# Adafruit_NeoPixel_FeatherWing.net
KiCad netlist of a schematic drawn in EAGLE
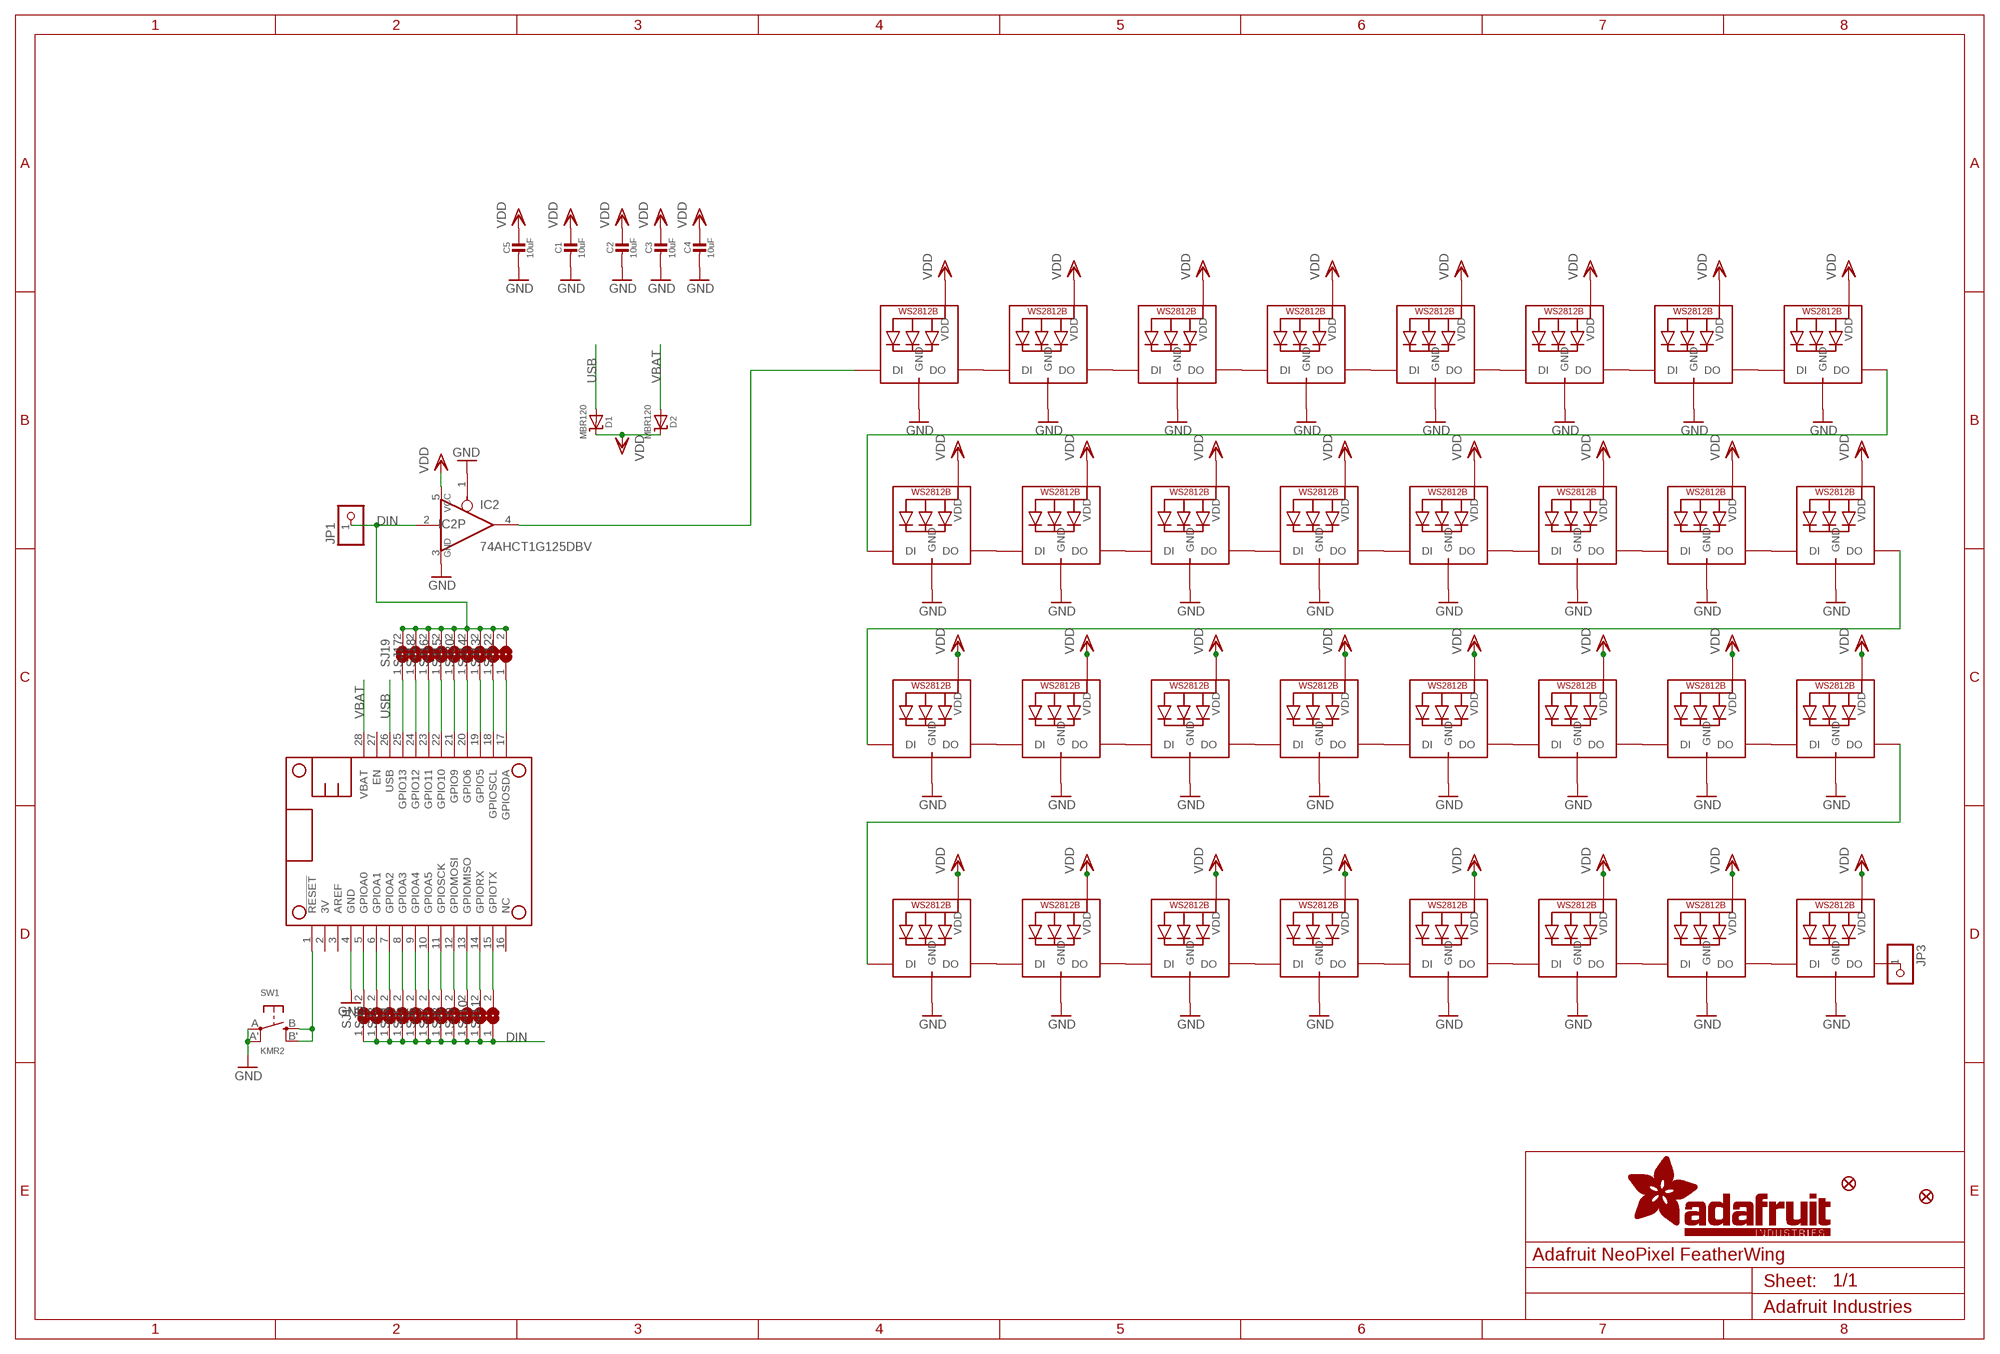
[diagram p0: schematic, sheet 1]

(export (version "E")
  (design (tool "Eeschema 10.0.6"))
  (components
    (comp (ref "C1")
      (value "10uF")
      (footprint "eagle-import:0805-NO")
      (libsource (lib "eagle-import") (part "CAP_CERAMIC0805-NOOUTLINE"))
    )
    (comp (ref "C2")
      (value "10uF")
      (footprint "eagle-import:0805-NO")
      (libsource (lib "eagle-import") (part "CAP_CERAMIC0805-NOOUTLINE"))
    )
    (comp (ref "C3")
      (value "10uF")
      (footprint "eagle-import:0805-NO")
      (libsource (lib "eagle-import") (part "CAP_CERAMIC0805-NOOUTLINE"))
    )
    (comp (ref "C4")
      (value "10uF")
      (footprint "eagle-import:0805-NO")
      (libsource (lib "eagle-import") (part "CAP_CERAMIC0805-NOOUTLINE"))
    )
    (comp (ref "C5")
      (value "10uF")
      (footprint "eagle-import:0805-NO")
      (libsource (lib "eagle-import") (part "CAP_CERAMIC0805-NOOUTLINE"))
    )
    (comp (ref "D1")
      (value "MBR120")
      (footprint "eagle-import:SOD-123")
      (libsource (lib "eagle-import") (part "DIODE-SCHOTTKYSOD-123"))
    )
    (comp (ref "D2")
      (value "MBR120")
      (footprint "eagle-import:SOD-123")
      (libsource (lib "eagle-import") (part "DIODE-SCHOTTKYSOD-123"))
    )
    (comp (ref "FID1")
      (value "FIDUCIAL\"\"")
      (footprint "eagle-import:FIDUCIAL_1MM")
      (libsource (lib "eagle-import") (part "FIDUCIAL{dblquote}{dblquote}"))
    )
    (comp (ref "FID3")
      (value "FIDUCIAL\"\"")
      (footprint "eagle-import:FIDUCIAL_1MM")
      (libsource (lib "eagle-import") (part "FIDUCIAL{dblquote}{dblquote}"))
    )
    (comp (ref "IC2")
      (value "74AHCT1G125DBV")
      (footprint "eagle-import:SOT23-5")
      (libsource (lib "eagle-import") (part "741G125DBVAHCT"))
    )
    (comp (ref "JP1")
      (value "HEADER-1X1ROUND")
      (footprint "eagle-import:1X01_ROUND")
      (libsource (lib "eagle-import") (part "HEADER-1X1ROUND"))
    )
    (comp (ref "JP3")
      (value "HEADER-1X1ROUND")
      (footprint "eagle-import:1X01_ROUND")
      (libsource (lib "eagle-import") (part "HEADER-1X1ROUND"))
    )
    (comp (ref "LED1")
      (value "WS2812B3535")
      (footprint "eagle-import:LED3535")
      (libsource (lib "eagle-import") (part "WS2812B3535"))
    )
    (comp (ref "LED2")
      (value "WS2812B3535")
      (footprint "eagle-import:LED3535")
      (libsource (lib "eagle-import") (part "WS2812B3535"))
    )
    (comp (ref "LED3")
      (value "WS2812B3535")
      (footprint "eagle-import:LED3535")
      (libsource (lib "eagle-import") (part "WS2812B3535"))
    )
    (comp (ref "LED4")
      (value "WS2812B3535")
      (footprint "eagle-import:LED3535")
      (libsource (lib "eagle-import") (part "WS2812B3535"))
    )
    (comp (ref "LED5")
      (value "WS2812B3535")
      (footprint "eagle-import:LED3535")
      (libsource (lib "eagle-import") (part "WS2812B3535"))
    )
    (comp (ref "LED6")
      (value "WS2812B3535")
      (footprint "eagle-import:LED3535")
      (libsource (lib "eagle-import") (part "WS2812B3535"))
    )
    (comp (ref "LED7")
      (value "WS2812B3535")
      (footprint "eagle-import:LED3535")
      (libsource (lib "eagle-import") (part "WS2812B3535"))
    )
    (comp (ref "LED8")
      (value "WS2812B3535")
      (footprint "eagle-import:LED3535")
      (libsource (lib "eagle-import") (part "WS2812B3535"))
    )
    (comp (ref "LED9")
      (value "WS2812B3535")
      (footprint "eagle-import:LED3535")
      (libsource (lib "eagle-import") (part "WS2812B3535"))
    )
    (comp (ref "LED10")
      (value "WS2812B3535")
      (footprint "eagle-import:LED3535")
      (libsource (lib "eagle-import") (part "WS2812B3535"))
    )
    (comp (ref "LED11")
      (value "WS2812B3535")
      (footprint "eagle-import:LED3535")
      (libsource (lib "eagle-import") (part "WS2812B3535"))
    )
    (comp (ref "LED12")
      (value "WS2812B3535")
      (footprint "eagle-import:LED3535")
      (libsource (lib "eagle-import") (part "WS2812B3535"))
    )
    (comp (ref "LED13")
      (value "WS2812B3535")
      (footprint "eagle-import:LED3535")
      (libsource (lib "eagle-import") (part "WS2812B3535"))
    )
    (comp (ref "LED14")
      (value "WS2812B3535")
      (footprint "eagle-import:LED3535")
      (libsource (lib "eagle-import") (part "WS2812B3535"))
    )
    (comp (ref "LED15")
      (value "WS2812B3535")
      (footprint "eagle-import:LED3535")
      (libsource (lib "eagle-import") (part "WS2812B3535"))
    )
    (comp (ref "LED16")
      (value "WS2812B3535")
      (footprint "eagle-import:LED3535")
      (libsource (lib "eagle-import") (part "WS2812B3535"))
    )
    (comp (ref "LED17")
      (value "WS2812B3535")
      (footprint "eagle-import:LED3535")
      (libsource (lib "eagle-import") (part "WS2812B3535"))
    )
    (comp (ref "LED18")
      (value "WS2812B3535")
      (footprint "eagle-import:LED3535")
      (libsource (lib "eagle-import") (part "WS2812B3535"))
    )
    (comp (ref "LED19")
      (value "WS2812B3535")
      (footprint "eagle-import:LED3535")
      (libsource (lib "eagle-import") (part "WS2812B3535"))
    )
    (comp (ref "LED20")
      (value "WS2812B3535")
      (footprint "eagle-import:LED3535")
      (libsource (lib "eagle-import") (part "WS2812B3535"))
    )
    (comp (ref "LED21")
      (value "WS2812B3535")
      (footprint "eagle-import:LED3535")
      (libsource (lib "eagle-import") (part "WS2812B3535"))
    )
    (comp (ref "LED22")
      (value "WS2812B3535")
      (footprint "eagle-import:LED3535")
      (libsource (lib "eagle-import") (part "WS2812B3535"))
    )
    (comp (ref "LED23")
      (value "WS2812B3535")
      (footprint "eagle-import:LED3535")
      (libsource (lib "eagle-import") (part "WS2812B3535"))
    )
    (comp (ref "LED24")
      (value "WS2812B3535")
      (footprint "eagle-import:LED3535")
      (libsource (lib "eagle-import") (part "WS2812B3535"))
    )
    (comp (ref "LED25")
      (value "WS2812B3535")
      (footprint "eagle-import:LED3535")
      (libsource (lib "eagle-import") (part "WS2812B3535"))
    )
    (comp (ref "LED26")
      (value "WS2812B3535")
      (footprint "eagle-import:LED3535")
      (libsource (lib "eagle-import") (part "WS2812B3535"))
    )
    (comp (ref "LED27")
      (value "WS2812B3535")
      (footprint "eagle-import:LED3535")
      (libsource (lib "eagle-import") (part "WS2812B3535"))
    )
    (comp (ref "LED28")
      (value "WS2812B3535")
      (footprint "eagle-import:LED3535")
      (libsource (lib "eagle-import") (part "WS2812B3535"))
    )
    (comp (ref "LED29")
      (value "WS2812B3535")
      (footprint "eagle-import:LED3535")
      (libsource (lib "eagle-import") (part "WS2812B3535"))
    )
    (comp (ref "LED30")
      (value "WS2812B3535")
      (footprint "eagle-import:LED3535")
      (libsource (lib "eagle-import") (part "WS2812B3535"))
    )
    (comp (ref "LED31")
      (value "WS2812B3535")
      (footprint "eagle-import:LED3535")
      (libsource (lib "eagle-import") (part "WS2812B3535"))
    )
    (comp (ref "LED32")
      (value "WS2812B3535")
      (footprint "eagle-import:LED3535")
      (libsource (lib "eagle-import") (part "WS2812B3535"))
    )
    (comp (ref "MS1")
      (value "FEATHERWING")
      (footprint "eagle-import:FEATHERWING")
      (libsource (lib "eagle-import") (part "FEATHERWING"))
    )
    (comp (ref "SJ1")
      (value "SOLDERJUMPER")
      (footprint "eagle-import:SOLDERJUMPER_ARROW_NOPASTE")
      (libsource (lib "eagle-import") (part "SOLDERJUMPER"))
    )
    (comp (ref "SJ2")
      (value "SOLDERJUMPER")
      (footprint "eagle-import:SOLDERJUMPER_ARROW_NOPASTE")
      (libsource (lib "eagle-import") (part "SOLDERJUMPER"))
    )
    (comp (ref "SJ3")
      (value "SOLDERJUMPER")
      (footprint "eagle-import:SOLDERJUMPER_ARROW_NOPASTE")
      (libsource (lib "eagle-import") (part "SOLDERJUMPER"))
    )
    (comp (ref "SJ4")
      (value "SOLDERJUMPER")
      (footprint "eagle-import:SOLDERJUMPER_ARROW_NOPASTE")
      (libsource (lib "eagle-import") (part "SOLDERJUMPER"))
    )
    (comp (ref "SJ5")
      (value "SOLDERJUMPER")
      (footprint "eagle-import:SOLDERJUMPER_ARROW_NOPASTE")
      (libsource (lib "eagle-import") (part "SOLDERJUMPER"))
    )
    (comp (ref "SJ6")
      (value "SOLDERJUMPER")
      (footprint "eagle-import:SOLDERJUMPER_ARROW_NOPASTE")
      (libsource (lib "eagle-import") (part "SOLDERJUMPER"))
    )
    (comp (ref "SJ7")
      (value "SOLDERJUMPER")
      (footprint "eagle-import:SOLDERJUMPER_ARROW_NOPASTE")
      (libsource (lib "eagle-import") (part "SOLDERJUMPER"))
    )
    (comp (ref "SJ8")
      (value "SOLDERJUMPER")
      (footprint "eagle-import:SOLDERJUMPER_ARROW_NOPASTE")
      (libsource (lib "eagle-import") (part "SOLDERJUMPER"))
    )
    (comp (ref "SJ9")
      (value "SOLDERJUMPER")
      (footprint "eagle-import:SOLDERJUMPER_ARROW_NOPASTE")
      (libsource (lib "eagle-import") (part "SOLDERJUMPER"))
    )
    (comp (ref "SJ10")
      (value "SOLDERJUMPER")
      (footprint "eagle-import:SOLDERJUMPER_ARROW_NOPASTE")
      (libsource (lib "eagle-import") (part "SOLDERJUMPER"))
    )
    (comp (ref "SJ11")
      (value "SOLDERJUMPER")
      (footprint "eagle-import:SOLDERJUMPER_ARROW_NOPASTE")
      (libsource (lib "eagle-import") (part "SOLDERJUMPER"))
    )
    (comp (ref "SJ12")
      (value "SOLDERJUMPER")
      (footprint "eagle-import:SOLDERJUMPER_ARROW_NOPASTE")
      (libsource (lib "eagle-import") (part "SOLDERJUMPER"))
    )
    (comp (ref "SJ13")
      (value "SOLDERJUMPER")
      (footprint "eagle-import:SOLDERJUMPER_ARROW_NOPASTE")
      (libsource (lib "eagle-import") (part "SOLDERJUMPER"))
    )
    (comp (ref "SJ14")
      (value "SOLDERJUMPER")
      (footprint "eagle-import:SOLDERJUMPER_ARROW_NOPASTE")
      (libsource (lib "eagle-import") (part "SOLDERJUMPER"))
    )
    (comp (ref "SJ15")
      (value "SOLDERJUMPER")
      (footprint "eagle-import:SOLDERJUMPER_ARROW_NOPASTE")
      (libsource (lib "eagle-import") (part "SOLDERJUMPER"))
    )
    (comp (ref "SJ16")
      (value "SOLDERJUMPER")
      (footprint "eagle-import:SOLDERJUMPER_ARROW_NOPASTE")
      (libsource (lib "eagle-import") (part "SOLDERJUMPER"))
    )
    (comp (ref "SJ17")
      (value "SOLDERJUMPER")
      (footprint "eagle-import:SOLDERJUMPER_ARROW_NOPASTE")
      (libsource (lib "eagle-import") (part "SOLDERJUMPER"))
    )
    (comp (ref "SJ18")
      (value "SOLDERJUMPER")
      (footprint "eagle-import:SOLDERJUMPER_ARROW_NOPASTE")
      (libsource (lib "eagle-import") (part "SOLDERJUMPER"))
    )
    (comp (ref "SJ19")
      (value "SOLDERJUMPER")
      (footprint "eagle-import:SOLDERJUMPER_ARROW_NOPASTE")
      (libsource (lib "eagle-import") (part "SOLDERJUMPER"))
    )
    (comp (ref "SJ20")
      (value "SOLDERJUMPERCLOSED")
      (footprint "eagle-import:SOLDERJUMPER_CLOSEDWIRE")
      (libsource (lib "eagle-import") (part "SOLDERJUMPERCLOSED"))
    )
    (comp (ref "SW1")
      (value "KMR2")
      (footprint "eagle-import:BTN_KMR2_4.6X2.8")
      (libsource (lib "eagle-import") (part "SWITCH_TACT_SMT4.6X2.8"))
    )
  )
  (nets
    (net (code "1") (name "/3V") (class "Default")
      (node (ref "MS1") (pin "2") (pinfunction "3V_2") (pintype "power_in"))
    )
    (net (code "2") (name "/DIN") (class "Default")
      (node (ref "IC2") (pin "2") (pinfunction "I_2") (pintype "input"))
      (node (ref "JP1") (pin "1") (pinfunction "1_1") (pintype "passive"))
      (node (ref "SJ1") (pin "1") (pinfunction "1_1") (pintype "passive"))
      (node (ref "SJ10") (pin "1") (pinfunction "1_1") (pintype "passive"))
      (node (ref "SJ11") (pin "1") (pinfunction "1_1") (pintype "passive"))
      (node (ref "SJ12") (pin "2") (pinfunction "2_2") (pintype "passive"))
      (node (ref "SJ13") (pin "2") (pinfunction "2_2") (pintype "passive"))
      (node (ref "SJ14") (pin "2") (pinfunction "2_2") (pintype "passive"))
      (node (ref "SJ15") (pin "2") (pinfunction "2_2") (pintype "passive"))
      (node (ref "SJ16") (pin "2") (pinfunction "2_2") (pintype "passive"))
      (node (ref "SJ17") (pin "2") (pinfunction "2_2") (pintype "passive"))
      (node (ref "SJ18") (pin "2") (pinfunction "2_2") (pintype "passive"))
      (node (ref "SJ19") (pin "2") (pinfunction "2_2") (pintype "passive"))
      (node (ref "SJ2") (pin "1") (pinfunction "1_1") (pintype "passive"))
      (node (ref "SJ20") (pin "2") (pinfunction "2_2") (pintype "passive"))
      (node (ref "SJ3") (pin "1") (pinfunction "1_1") (pintype "passive"))
      (node (ref "SJ4") (pin "1") (pinfunction "1_1") (pintype "passive"))
      (node (ref "SJ5") (pin "1") (pinfunction "1_1") (pintype "passive"))
      (node (ref "SJ6") (pin "1") (pinfunction "1_1") (pintype "passive"))
      (node (ref "SJ7") (pin "1") (pinfunction "1_1") (pintype "passive"))
      (node (ref "SJ8") (pin "1") (pinfunction "1_1") (pintype "passive"))
      (node (ref "SJ9") (pin "1") (pinfunction "1_1") (pintype "passive"))
    )
    (net (code "3") (name "/USB") (class "Default")
      (node (ref "D1") (pin "A") (pinfunction "A_A") (pintype "passive"))
      (node (ref "MS1") (pin "26") (pinfunction "USB_26") (pintype "power_in"))
    )
    (net (code "4") (name "/VBAT") (class "Default")
      (node (ref "D2") (pin "A") (pinfunction "A_A") (pintype "passive"))
      (node (ref "MS1") (pin "28") (pinfunction "VBAT_28") (pintype "power_in"))
    )
    (net (code "5") (name "GND") (class "Default")
      (node (ref "C1") (pin "2") (pinfunction "2_2") (pintype "passive"))
      (node (ref "C2") (pin "2") (pinfunction "2_2") (pintype "passive"))
      (node (ref "C3") (pin "2") (pinfunction "2_2") (pintype "passive"))
      (node (ref "C4") (pin "2") (pinfunction "2_2") (pintype "passive"))
      (node (ref "C5") (pin "2") (pinfunction "2_2") (pintype "passive"))
      (node (ref "IC2") (pin "1") (pinfunction "OE_1") (pintype "input"))
      (node (ref "IC2") (pin "3") (pinfunction "GND_3") (pintype "power_in"))
      (node (ref "LED1") (pin "4") (pinfunction "GND_4") (pintype "power_in"))
      (node (ref "LED10") (pin "4") (pinfunction "GND_4") (pintype "power_in"))
      (node (ref "LED11") (pin "4") (pinfunction "GND_4") (pintype "power_in"))
      (node (ref "LED12") (pin "4") (pinfunction "GND_4") (pintype "power_in"))
      (node (ref "LED13") (pin "4") (pinfunction "GND_4") (pintype "power_in"))
      (node (ref "LED14") (pin "4") (pinfunction "GND_4") (pintype "power_in"))
      (node (ref "LED15") (pin "4") (pinfunction "GND_4") (pintype "power_in"))
      (node (ref "LED16") (pin "4") (pinfunction "GND_4") (pintype "power_in"))
      (node (ref "LED17") (pin "4") (pinfunction "GND_4") (pintype "power_in"))
      (node (ref "LED18") (pin "4") (pinfunction "GND_4") (pintype "power_in"))
      (node (ref "LED19") (pin "4") (pinfunction "GND_4") (pintype "power_in"))
      (node (ref "LED2") (pin "4") (pinfunction "GND_4") (pintype "power_in"))
      (node (ref "LED20") (pin "4") (pinfunction "GND_4") (pintype "power_in"))
      (node (ref "LED21") (pin "4") (pinfunction "GND_4") (pintype "power_in"))
      (node (ref "LED22") (pin "4") (pinfunction "GND_4") (pintype "power_in"))
      (node (ref "LED23") (pin "4") (pinfunction "GND_4") (pintype "power_in"))
      (node (ref "LED24") (pin "4") (pinfunction "GND_4") (pintype "power_in"))
      (node (ref "LED25") (pin "4") (pinfunction "GND_4") (pintype "power_in"))
      (node (ref "LED26") (pin "4") (pinfunction "GND_4") (pintype "power_in"))
      (node (ref "LED27") (pin "4") (pinfunction "GND_4") (pintype "power_in"))
      (node (ref "LED28") (pin "4") (pinfunction "GND_4") (pintype "power_in"))
      (node (ref "LED29") (pin "4") (pinfunction "GND_4") (pintype "power_in"))
      (node (ref "LED3") (pin "4") (pinfunction "GND_4") (pintype "power_in"))
      (node (ref "LED30") (pin "4") (pinfunction "GND_4") (pintype "power_in"))
      (node (ref "LED31") (pin "4") (pinfunction "GND_4") (pintype "power_in"))
      (node (ref "LED32") (pin "4") (pinfunction "GND_4") (pintype "power_in"))
      (node (ref "LED4") (pin "4") (pinfunction "GND_4") (pintype "power_in"))
      (node (ref "LED5") (pin "4") (pinfunction "GND_4") (pintype "power_in"))
      (node (ref "LED6") (pin "4") (pinfunction "GND_4") (pintype "power_in"))
      (node (ref "LED7") (pin "4") (pinfunction "GND_4") (pintype "power_in"))
      (node (ref "LED8") (pin "4") (pinfunction "GND_4") (pintype "power_in"))
      (node (ref "LED9") (pin "4") (pinfunction "GND_4") (pintype "power_in"))
      (node (ref "MS1") (pin "4") (pinfunction "GND_4") (pintype "power_in"))
      (node (ref "SW1") (pin "A") (pinfunction "P_A") (pintype "passive"))
      (node (ref "SW1") (pin "A'") (pinfunction "P1_A'") (pintype "passive"))
    )
    (net (code "6") (name "Net-(IC2A-O)") (class "Default")
      (node (ref "IC2") (pin "4") (pinfunction "O_4") (pintype "tri_state"))
      (node (ref "LED1") (pin "1") (pinfunction "DI_1") (pintype "input"))
    )
    (net (code "7") (name "Net-(LED1-DO)") (class "Default")
      (node (ref "LED1") (pin "3") (pinfunction "DO_3") (pintype "output"))
      (node (ref "LED2") (pin "1") (pinfunction "DI_1") (pintype "input"))
    )
    (net (code "8") (name "Net-(LED2-DO)") (class "Default")
      (node (ref "LED2") (pin "3") (pinfunction "DO_3") (pintype "output"))
      (node (ref "LED3") (pin "1") (pinfunction "DI_1") (pintype "input"))
    )
    (net (code "9") (name "Net-(LED3-DO)") (class "Default")
      (node (ref "LED3") (pin "3") (pinfunction "DO_3") (pintype "output"))
      (node (ref "LED4") (pin "1") (pinfunction "DI_1") (pintype "input"))
    )
    (net (code "10") (name "Net-(LED4-DO)") (class "Default")
      (node (ref "LED4") (pin "3") (pinfunction "DO_3") (pintype "output"))
      (node (ref "LED5") (pin "1") (pinfunction "DI_1") (pintype "input"))
    )
    (net (code "11") (name "Net-(LED5-DO)") (class "Default")
      (node (ref "LED5") (pin "3") (pinfunction "DO_3") (pintype "output"))
      (node (ref "LED6") (pin "1") (pinfunction "DI_1") (pintype "input"))
    )
    (net (code "12") (name "Net-(LED7-DO)") (class "Default")
      (node (ref "LED7") (pin "3") (pinfunction "DO_3") (pintype "output"))
      (node (ref "LED8") (pin "1") (pinfunction "DI_1") (pintype "input"))
    )
    (net (code "13") (name "Net-(LED8-DO)") (class "Default")
      (node (ref "LED8") (pin "3") (pinfunction "DO_3") (pintype "output"))
      (node (ref "LED9") (pin "1") (pinfunction "DI_1") (pintype "input"))
    )
    (net (code "14") (name "Net-(LED10-DI)") (class "Default")
      (node (ref "LED10") (pin "1") (pinfunction "DI_1") (pintype "input"))
      (node (ref "LED9") (pin "3") (pinfunction "DO_3") (pintype "output"))
    )
    (net (code "15") (name "Net-(LED10-DO)") (class "Default")
      (node (ref "LED10") (pin "3") (pinfunction "DO_3") (pintype "output"))
      (node (ref "LED11") (pin "1") (pinfunction "DI_1") (pintype "input"))
    )
    (net (code "16") (name "Net-(LED11-DO)") (class "Default")
      (node (ref "LED11") (pin "3") (pinfunction "DO_3") (pintype "output"))
      (node (ref "LED12") (pin "1") (pinfunction "DI_1") (pintype "input"))
    )
    (net (code "17") (name "Net-(LED12-DO)") (class "Default")
      (node (ref "LED12") (pin "3") (pinfunction "DO_3") (pintype "output"))
      (node (ref "LED27") (pin "1") (pinfunction "DI_1") (pintype "input"))
    )
    (net (code "18") (name "Net-(LED13-DI)") (class "Default")
      (node (ref "LED13") (pin "1") (pinfunction "DI_1") (pintype "input"))
      (node (ref "LED28") (pin "3") (pinfunction "DO_3") (pintype "output"))
    )
    (net (code "19") (name "Net-(LED13-DO)") (class "Default")
      (node (ref "LED13") (pin "3") (pinfunction "DO_3") (pintype "output"))
      (node (ref "LED14") (pin "1") (pinfunction "DI_1") (pintype "input"))
    )
    (net (code "20") (name "Net-(LED14-DO)") (class "Default")
      (node (ref "LED14") (pin "3") (pinfunction "DO_3") (pintype "output"))
      (node (ref "LED15") (pin "1") (pinfunction "DI_1") (pintype "input"))
    )
    (net (code "21") (name "Net-(LED15-DO)") (class "Default")
      (node (ref "LED15") (pin "3") (pinfunction "DO_3") (pintype "output"))
      (node (ref "LED16") (pin "1") (pinfunction "DI_1") (pintype "input"))
    )
    (net (code "22") (name "Net-(LED16-DO)") (class "Default")
      (node (ref "LED16") (pin "3") (pinfunction "DO_3") (pintype "output"))
      (node (ref "LED17") (pin "1") (pinfunction "DI_1") (pintype "input"))
    )
    (net (code "23") (name "Net-(LED17-DO)") (class "Default")
      (node (ref "LED17") (pin "3") (pinfunction "DO_3") (pintype "output"))
      (node (ref "LED18") (pin "1") (pinfunction "DI_1") (pintype "input"))
    )
    (net (code "24") (name "Net-(LED18-DO)") (class "Default")
      (node (ref "LED18") (pin "3") (pinfunction "DO_3") (pintype "output"))
      (node (ref "LED29") (pin "1") (pinfunction "DI_1") (pintype "input"))
    )
    (net (code "25") (name "Net-(LED19-DI)") (class "Default")
      (node (ref "LED19") (pin "1") (pinfunction "DI_1") (pintype "input"))
      (node (ref "LED30") (pin "3") (pinfunction "DO_3") (pintype "output"))
    )
    (net (code "26") (name "Net-(LED19-DO)") (class "Default")
      (node (ref "LED19") (pin "3") (pinfunction "DO_3") (pintype "output"))
      (node (ref "LED20") (pin "1") (pinfunction "DI_1") (pintype "input"))
    )
    (net (code "27") (name "Net-(LED20-DO)") (class "Default")
      (node (ref "LED20") (pin "3") (pinfunction "DO_3") (pintype "output"))
      (node (ref "LED21") (pin "1") (pinfunction "DI_1") (pintype "input"))
    )
    (net (code "28") (name "Net-(LED21-DO)") (class "Default")
      (node (ref "LED21") (pin "3") (pinfunction "DO_3") (pintype "output"))
      (node (ref "LED22") (pin "1") (pinfunction "DI_1") (pintype "input"))
    )
    (net (code "29") (name "Net-(LED22-DO)") (class "Default")
      (node (ref "LED22") (pin "3") (pinfunction "DO_3") (pintype "output"))
      (node (ref "LED23") (pin "1") (pinfunction "DI_1") (pintype "input"))
    )
    (net (code "30") (name "Net-(LED23-DO)") (class "Default")
      (node (ref "LED23") (pin "3") (pinfunction "DO_3") (pintype "output"))
      (node (ref "LED24") (pin "1") (pinfunction "DI_1") (pintype "input"))
    )
    (net (code "31") (name "Net-(LED24-DO)") (class "Default")
      (node (ref "LED24") (pin "3") (pinfunction "DO_3") (pintype "output"))
      (node (ref "LED31") (pin "1") (pinfunction "DI_1") (pintype "input"))
    )
    (net (code "32") (name "Net-(LED25-DI)") (class "Default")
      (node (ref "LED25") (pin "1") (pinfunction "DI_1") (pintype "input"))
      (node (ref "LED6") (pin "3") (pinfunction "DO_3") (pintype "output"))
    )
    (net (code "33") (name "Net-(LED25-DO)") (class "Default")
      (node (ref "LED25") (pin "3") (pinfunction "DO_3") (pintype "output"))
      (node (ref "LED26") (pin "1") (pinfunction "DI_1") (pintype "input"))
    )
    (net (code "34") (name "Net-(LED26-DO)") (class "Default")
      (node (ref "LED26") (pin "3") (pinfunction "DO_3") (pintype "output"))
      (node (ref "LED7") (pin "1") (pinfunction "DI_1") (pintype "input"))
    )
    (net (code "35") (name "Net-(LED27-DO)") (class "Default")
      (node (ref "LED27") (pin "3") (pinfunction "DO_3") (pintype "output"))
      (node (ref "LED28") (pin "1") (pinfunction "DI_1") (pintype "input"))
    )
    (net (code "36") (name "Net-(LED29-DO)") (class "Default")
      (node (ref "LED29") (pin "3") (pinfunction "DO_3") (pintype "output"))
      (node (ref "LED30") (pin "1") (pinfunction "DI_1") (pintype "input"))
    )
    (net (code "37") (name "Net-(LED31-DO)") (class "Default")
      (node (ref "LED31") (pin "3") (pinfunction "DO_3") (pintype "output"))
      (node (ref "LED32") (pin "1") (pinfunction "DI_1") (pintype "input"))
    )
    (net (code "38") (name "Net-(LED32-DO)") (class "Default")
      (node (ref "JP3") (pin "1") (pinfunction "1_1") (pintype "passive"))
      (node (ref "LED32") (pin "3") (pinfunction "DO_3") (pintype "output"))
    )
    (net (code "39") (name "Net-(MS1-GPIO5)") (class "Default")
      (node (ref "MS1") (pin "19") (pinfunction "GPIO5_19") (pintype "bidirectional"))
      (node (ref "SJ14") (pin "1") (pinfunction "1_1") (pintype "passive"))
    )
    (net (code "40") (name "Net-(MS1-GPIO6)") (class "Default")
      (node (ref "MS1") (pin "20") (pinfunction "GPIO6_20") (pintype "bidirectional"))
      (node (ref "SJ20") (pin "1") (pinfunction "1_1") (pintype "passive"))
    )
    (net (code "41") (name "Net-(MS1-GPIO9)") (class "Default")
      (node (ref "MS1") (pin "21") (pinfunction "GPIO9_21") (pintype "bidirectional"))
      (node (ref "SJ15") (pin "1") (pinfunction "1_1") (pintype "passive"))
    )
    (net (code "42") (name "Net-(MS1-GPIO10)") (class "Default")
      (node (ref "MS1") (pin "22") (pinfunction "GPIO10_22") (pintype "bidirectional"))
      (node (ref "SJ16") (pin "1") (pinfunction "1_1") (pintype "passive"))
    )
    (net (code "43") (name "Net-(MS1-GPIO11)") (class "Default")
      (node (ref "MS1") (pin "23") (pinfunction "GPIO11_23") (pintype "bidirectional"))
      (node (ref "SJ18") (pin "1") (pinfunction "1_1") (pintype "passive"))
    )
    (net (code "44") (name "Net-(MS1-GPIO12)") (class "Default")
      (node (ref "MS1") (pin "24") (pinfunction "GPIO12_24") (pintype "bidirectional"))
      (node (ref "SJ17") (pin "1") (pinfunction "1_1") (pintype "passive"))
    )
    (net (code "45") (name "Net-(MS1-GPIO13)") (class "Default")
      (node (ref "MS1") (pin "25") (pinfunction "GPIO13_25") (pintype "bidirectional"))
      (node (ref "SJ19") (pin "1") (pinfunction "1_1") (pintype "passive"))
    )
    (net (code "46") (name "Net-(MS1-GPIOA0)") (class "Default")
      (node (ref "MS1") (pin "5") (pinfunction "GPIOA0_5") (pintype "bidirectional"))
      (node (ref "SJ1") (pin "2") (pinfunction "2_2") (pintype "passive"))
    )
    (net (code "47") (name "Net-(MS1-GPIOA1)") (class "Default")
      (node (ref "MS1") (pin "6") (pinfunction "GPIOA1_6") (pintype "bidirectional"))
      (node (ref "SJ2") (pin "2") (pinfunction "2_2") (pintype "passive"))
    )
    (net (code "48") (name "Net-(MS1-GPIOA2)") (class "Default")
      (node (ref "MS1") (pin "7") (pinfunction "GPIOA2_7") (pintype "bidirectional"))
      (node (ref "SJ3") (pin "2") (pinfunction "2_2") (pintype "passive"))
    )
    (net (code "49") (name "Net-(MS1-GPIOA3)") (class "Default")
      (node (ref "MS1") (pin "8") (pinfunction "GPIOA3_8") (pintype "bidirectional"))
      (node (ref "SJ4") (pin "2") (pinfunction "2_2") (pintype "passive"))
    )
    (net (code "50") (name "Net-(MS1-GPIOA4)") (class "Default")
      (node (ref "MS1") (pin "9") (pinfunction "GPIOA4_9") (pintype "bidirectional"))
      (node (ref "SJ5") (pin "2") (pinfunction "2_2") (pintype "passive"))
    )
    (net (code "51") (name "Net-(MS1-GPIOA5)") (class "Default")
      (node (ref "MS1") (pin "10") (pinfunction "GPIOA5_10") (pintype "bidirectional"))
      (node (ref "SJ6") (pin "2") (pinfunction "2_2") (pintype "passive"))
    )
    (net (code "52") (name "Net-(MS1-GPIOMISO)") (class "Default")
      (node (ref "MS1") (pin "13") (pinfunction "GPIOMISO_13") (pintype "bidirectional"))
      (node (ref "SJ9") (pin "2") (pinfunction "2_2") (pintype "passive"))
    )
    (net (code "53") (name "Net-(MS1-GPIOMOSI)") (class "Default")
      (node (ref "MS1") (pin "12") (pinfunction "GPIOMOSI_12") (pintype "bidirectional"))
      (node (ref "SJ8") (pin "2") (pinfunction "2_2") (pintype "passive"))
    )
    (net (code "54") (name "Net-(MS1-GPIORX)") (class "Default")
      (node (ref "MS1") (pin "14") (pinfunction "GPIORX_14") (pintype "bidirectional"))
      (node (ref "SJ10") (pin "2") (pinfunction "2_2") (pintype "passive"))
    )
    (net (code "55") (name "Net-(MS1-GPIOSCK)") (class "Default")
      (node (ref "MS1") (pin "11") (pinfunction "GPIOSCK_11") (pintype "bidirectional"))
      (node (ref "SJ7") (pin "2") (pinfunction "2_2") (pintype "passive"))
    )
    (net (code "56") (name "Net-(MS1-GPIOSCL)") (class "Default")
      (node (ref "MS1") (pin "18") (pinfunction "GPIOSCL_18") (pintype "bidirectional"))
      (node (ref "SJ13") (pin "1") (pinfunction "1_1") (pintype "passive"))
    )
    (net (code "57") (name "Net-(MS1-GPIOSDA)") (class "Default")
      (node (ref "MS1") (pin "17") (pinfunction "GPIOSDA_17") (pintype "bidirectional"))
      (node (ref "SJ12") (pin "1") (pinfunction "1_1") (pintype "passive"))
    )
    (net (code "58") (name "Net-(MS1-GPIOTX)") (class "Default")
      (node (ref "MS1") (pin "15") (pinfunction "GPIOTX_15") (pintype "bidirectional"))
      (node (ref "SJ11") (pin "2") (pinfunction "2_2") (pintype "passive"))
    )
    (net (code "59") (name "Net-(MS1-~{RESET})") (class "Default")
      (node (ref "MS1") (pin "1") (pinfunction "~{RESET}_1") (pintype "input"))
      (node (ref "SW1") (pin "B") (pinfunction "S_B") (pintype "passive"))
      (node (ref "SW1") (pin "B'") (pinfunction "S1_B'") (pintype "passive"))
    )
    (net (code "60") (name "VDD") (class "Default")
      (node (ref "C1") (pin "1") (pinfunction "1_1") (pintype "passive"))
      (node (ref "C2") (pin "1") (pinfunction "1_1") (pintype "passive"))
      (node (ref "C3") (pin "1") (pinfunction "1_1") (pintype "passive"))
      (node (ref "C4") (pin "1") (pinfunction "1_1") (pintype "passive"))
      (node (ref "C5") (pin "1") (pinfunction "1_1") (pintype "passive"))
      (node (ref "D1") (pin "C") (pinfunction "C_C") (pintype "passive"))
      (node (ref "D2") (pin "C") (pinfunction "C_C") (pintype "passive"))
      (node (ref "IC2") (pin "5") (pinfunction "VCC_5") (pintype "power_in"))
      (node (ref "LED1") (pin "2") (pinfunction "VDD_2") (pintype "power_in"))
      (node (ref "LED10") (pin "2") (pinfunction "VDD_2") (pintype "power_in"))
      (node (ref "LED11") (pin "2") (pinfunction "VDD_2") (pintype "power_in"))
      (node (ref "LED12") (pin "2") (pinfunction "VDD_2") (pintype "power_in"))
      (node (ref "LED13") (pin "2") (pinfunction "VDD_2") (pintype "power_in"))
      (node (ref "LED14") (pin "2") (pinfunction "VDD_2") (pintype "power_in"))
      (node (ref "LED15") (pin "2") (pinfunction "VDD_2") (pintype "power_in"))
      (node (ref "LED16") (pin "2") (pinfunction "VDD_2") (pintype "power_in"))
      (node (ref "LED17") (pin "2") (pinfunction "VDD_2") (pintype "power_in"))
      (node (ref "LED18") (pin "2") (pinfunction "VDD_2") (pintype "power_in"))
      (node (ref "LED19") (pin "2") (pinfunction "VDD_2") (pintype "power_in"))
      (node (ref "LED2") (pin "2") (pinfunction "VDD_2") (pintype "power_in"))
      (node (ref "LED20") (pin "2") (pinfunction "VDD_2") (pintype "power_in"))
      (node (ref "LED21") (pin "2") (pinfunction "VDD_2") (pintype "power_in"))
      (node (ref "LED22") (pin "2") (pinfunction "VDD_2") (pintype "power_in"))
      (node (ref "LED23") (pin "2") (pinfunction "VDD_2") (pintype "power_in"))
      (node (ref "LED24") (pin "2") (pinfunction "VDD_2") (pintype "power_in"))
      (node (ref "LED25") (pin "2") (pinfunction "VDD_2") (pintype "power_in"))
      (node (ref "LED26") (pin "2") (pinfunction "VDD_2") (pintype "power_in"))
      (node (ref "LED27") (pin "2") (pinfunction "VDD_2") (pintype "power_in"))
      (node (ref "LED28") (pin "2") (pinfunction "VDD_2") (pintype "power_in"))
      (node (ref "LED29") (pin "2") (pinfunction "VDD_2") (pintype "power_in"))
      (node (ref "LED3") (pin "2") (pinfunction "VDD_2") (pintype "power_in"))
      (node (ref "LED30") (pin "2") (pinfunction "VDD_2") (pintype "power_in"))
      (node (ref "LED31") (pin "2") (pinfunction "VDD_2") (pintype "power_in"))
      (node (ref "LED32") (pin "2") (pinfunction "VDD_2") (pintype "power_in"))
      (node (ref "LED4") (pin "2") (pinfunction "VDD_2") (pintype "power_in"))
      (node (ref "LED5") (pin "2") (pinfunction "VDD_2") (pintype "power_in"))
      (node (ref "LED6") (pin "2") (pinfunction "VDD_2") (pintype "power_in"))
      (node (ref "LED7") (pin "2") (pinfunction "VDD_2") (pintype "power_in"))
      (node (ref "LED8") (pin "2") (pinfunction "VDD_2") (pintype "power_in"))
      (node (ref "LED9") (pin "2") (pinfunction "VDD_2") (pintype "power_in"))
    )
    (net (code "61") (name "unconnected-(MS1-AREF-Pad3)") (class "Default")
      (node (ref "MS1") (pin "3") (pinfunction "AREF_3") (pintype "passive"))
    )
    (net (code "62") (name "unconnected-(MS1-EN-Pad27)") (class "Default")
      (node (ref "MS1") (pin "27") (pinfunction "EN_27") (pintype "passive"))
    )
    (net (code "63") (name "unconnected-(MS1-NC-Pad16)") (class "Default")
      (node (ref "MS1") (pin "16") (pinfunction "NC_16") (pintype "passive"))
    )
  )
)
